# 2020_Example_USBController.net
KiCad netlist of a schematic drawn in EAGLE
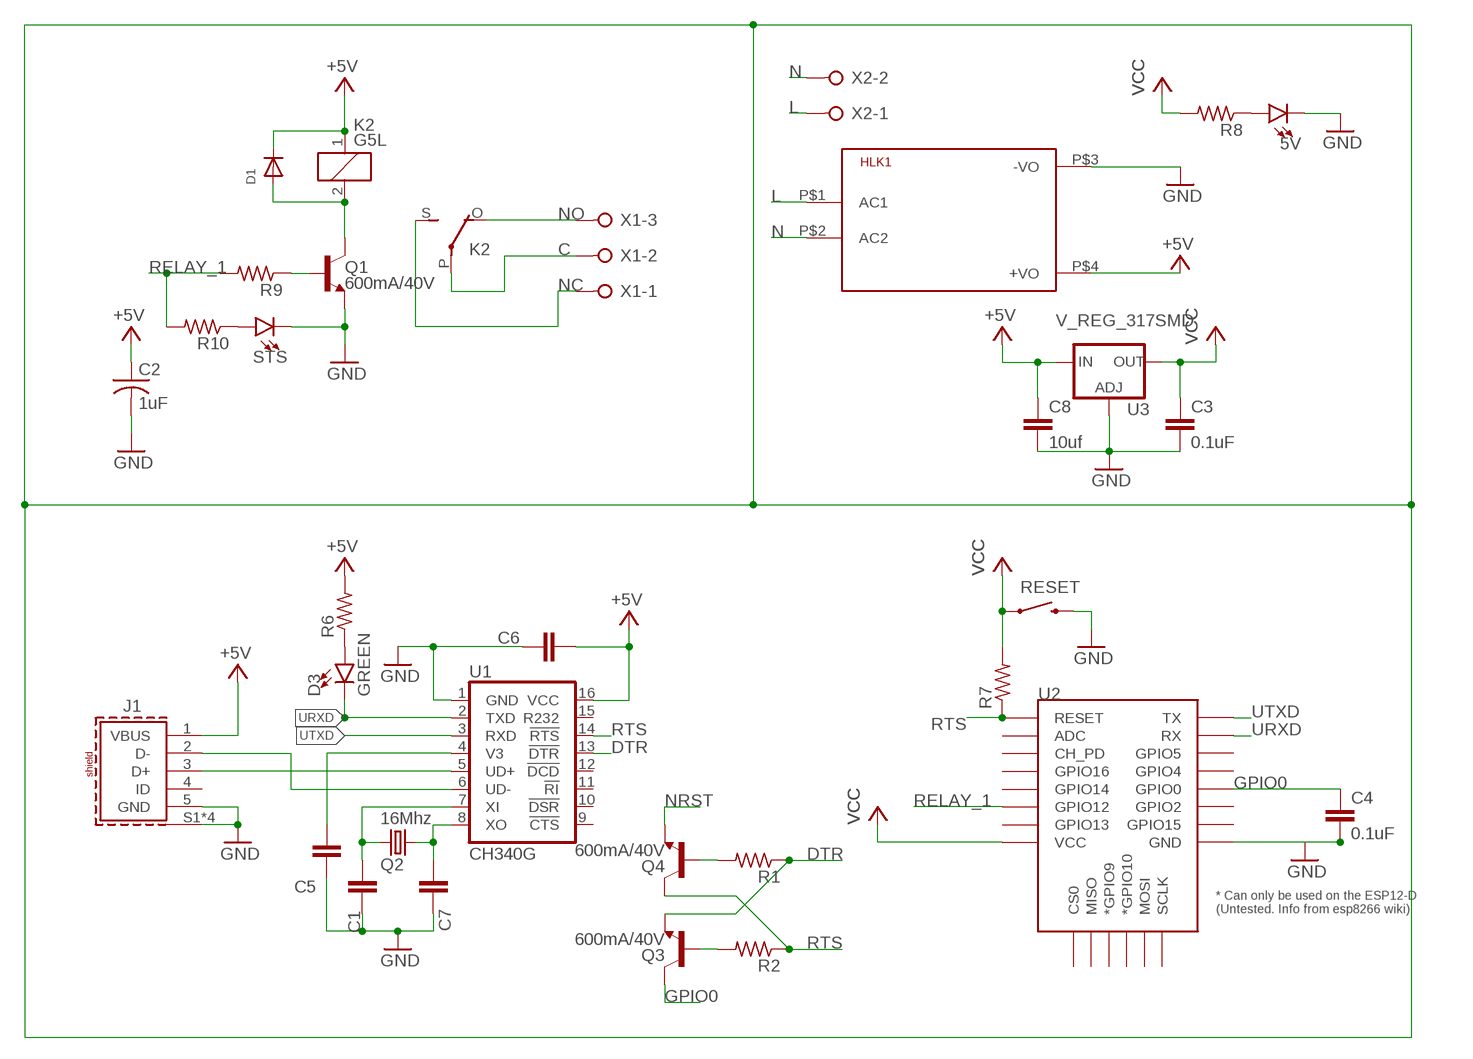
[diagram p0: schematic, sheet 1]

(export (version "E")
  (design (tool "Eeschema 10.0.6"))
  (components
    (comp (ref "5V")
      (value "LED-GREEN0603")
      (footprint "eagle-import:LED-0603")
      (libsource (lib "eagle-import") (part "LED-GREEN0603"))
    )
    (comp (ref "C1")
      (value "10pF")
      (footprint "eagle-import:C0805")
      (libsource (lib "eagle-import") (part "resistor_348_C-EUC0805"))
    )
    (comp (ref "C2")
      (value "1uF")
      (footprint "eagle-import:C0805K")
      (libsource (lib "eagle-import") (part "C-USC0805K"))
    )
    (comp (ref "C3")
      (value "0.1uF")
      (footprint "eagle-import:C0805")
      (libsource (lib "eagle-import") (part "C-EUC0805"))
    )
    (comp (ref "C4")
      (value "0.1uF")
      (footprint "eagle-import:C0805")
      (libsource (lib "eagle-import") (part "resistor_348_C-EUC0805"))
    )
    (comp (ref "C5")
      (value "10nF")
      (footprint "eagle-import:C0805")
      (libsource (lib "eagle-import") (part "resistor_348_C-EUC0805"))
    )
    (comp (ref "C6")
      (value "0.1uF")
      (footprint "eagle-import:C0805")
      (libsource (lib "eagle-import") (part "resistor_348_C-EUC0805"))
    )
    (comp (ref "C7")
      (value "10pF")
      (footprint "eagle-import:C0805")
      (libsource (lib "eagle-import") (part "resistor_348_C-EUC0805"))
    )
    (comp (ref "C8")
      (value "10uf")
      (footprint "eagle-import:C0805")
      (libsource (lib "eagle-import") (part "C-EUC0805"))
    )
    (comp (ref "D1")
      (value "DIODESOD-123")
      (footprint "eagle-import:SOD-123")
      (libsource (lib "eagle-import") (part "DIODESOD-123"))
    )
    (comp (ref "D3")
      (value "GREEN")
      (footprint "eagle-import:LED-0603")
      (libsource (lib "eagle-import") (part "LED-GREEN0603"))
    )
    (comp (ref "HLK1")
      (value "HLK-PM013W")
      (footprint "eagle-import:HLK-PM01")
      (libsource (lib "eagle-import") (part "HLK-PM013W"))
    )
    (comp (ref "J1")
      (value "629105150521")
      (footprint "eagle-import:629105150521")
      (libsource (lib "eagle-import") (part "629105150521"))
    )
    (comp (ref "K2")
      (value "G5L")
      (footprint "eagle-import:G5LE")
      (libsource (lib "eagle-import") (part "G5L"))
    )
    (comp (ref "Q1")
      (value "600mA/40V")
      (footprint "eagle-import:SOT23-3")
      (libsource (lib "eagle-import") (part "TRANS_NPN-MMBT2222AL"))
    )
    (comp (ref "Q2")
      (value "16Mhz")
      (footprint "eagle-import:5032_2P")
      (fields
        (field (name "MANUFACTURER") "Xinhunjing")
        (field (name "MPN") "5032/2P")
        (field (name "CREATED_BY") "PCBLayout.com")
      )
      (libsource (lib "eagle-import") (part "5032/2P"))
    )
    (comp (ref "Q3")
      (value "600mA/40V")
      (footprint "eagle-import:SOT23-3")
      (libsource (lib "eagle-import") (part "TRANS_NPN-MMBT2222AL"))
    )
    (comp (ref "Q4")
      (value "600mA/40V")
      (footprint "eagle-import:SOT23-3")
      (libsource (lib "eagle-import") (part "TRANS_NPN-MMBT2222AL"))
    )
    (comp (ref "R1")
      (value "R-US_R0805")
      (footprint "eagle-import:R0805")
      (libsource (lib "eagle-import") (part "R-US_R0805"))
    )
    (comp (ref "R2")
      (value "R-US_R0805")
      (footprint "eagle-import:R0805")
      (libsource (lib "eagle-import") (part "R-US_R0805"))
    )
    (comp (ref "R6")
      (value "R-US_R0805")
      (footprint "eagle-import:R0805")
      (libsource (lib "eagle-import") (part "R-US_R0805"))
    )
    (comp (ref "R7")
      (value "R-US_R0805")
      (footprint "eagle-import:R0805")
      (libsource (lib "eagle-import") (part "R-US_R0805"))
    )
    (comp (ref "R8")
      (value "R-US_R0805")
      (footprint "eagle-import:R0805")
      (libsource (lib "eagle-import") (part "R-US_R0805"))
    )
    (comp (ref "R9")
      (value "R-US_R0805")
      (footprint "eagle-import:R0805")
      (libsource (lib "eagle-import") (part "R-US_R0805"))
    )
    (comp (ref "R10")
      (value "R-US_R0805")
      (footprint "eagle-import:R0805")
      (libsource (lib "eagle-import") (part "R-US_R0805"))
    )
    (comp (ref "RESET")
      (value "RS032G05A3SM-SPST-MOMENTARY-SWSMD-1101NE")
      (footprint "eagle-import:TACTILE-SWITCH-1101NE")
      (libsource (lib "eagle-import") (part "RS032G05A3SM-SPST-MOMENTARY-SWSMD-1101NE"))
    )
    (comp (ref "STS")
      (value "LED-GREEN0603")
      (footprint "eagle-import:LED-0603")
      (libsource (lib "eagle-import") (part "LED-GREEN0603"))
    )
    (comp (ref "U1")
      (value "CH340G")
      (footprint "eagle-import:SO016")
      (libsource (lib "eagle-import") (part "CH340GSMD"))
    )
    (comp (ref "U2")
      (value "ESP12ESMD")
      (footprint "eagle-import:ESP12E-SMD")
      (libsource (lib "eagle-import") (part "ESP12ESMD"))
    )
    (comp (ref "U3")
      (value "V_REG_317SMD")
      (footprint "eagle-import:SOT223")
      (libsource (lib "eagle-import") (part "V_REG_317SMD"))
    )
    (comp (ref "X1")
      (value "W237-03P")
      (footprint "eagle-import:W237-133")
      (libsource (lib "eagle-import") (part "W237-03P"))
    )
    (comp (ref "X2")
      (value "W237-02P")
      (footprint "eagle-import:W237-132")
      (libsource (lib "eagle-import") (part "W237-02P"))
    )
  )
  (nets
    (net (code "1") (name "+5V") (class "Default")
      (node (ref "C2") (pin "1") (pinfunction "1_1") (pintype "passive"))
      (node (ref "C6") (pin "2") (pinfunction "2_2") (pintype "passive"))
      (node (ref "C8") (pin "1") (pinfunction "1_1") (pintype "passive"))
      (node (ref "D1") (pin "C") (pinfunction "C_C") (pintype "passive"))
      (node (ref "HLK1") (pin "P$4") (pinfunction "+VO_P$4") (pintype "bidirectional"))
      (node (ref "J1") (pin "1") (pinfunction "VBUS_1") (pintype "passive"))
      (node (ref "K2") (pin "1") (pinfunction "1_1") (pintype "passive"))
      (node (ref "R6") (pin "2") (pinfunction "2_2") (pintype "passive"))
      (node (ref "U1") (pin "16") (pinfunction "VCC_16") (pintype "bidirectional"))
      (node (ref "U3") (pin "3") (pinfunction "IN_3") (pintype "input"))
    )
    (net (code "2") (name "/C") (class "Default")
      (node (ref "K2") (pin "P") (pinfunction "P_P") (pintype "passive"))
      (node (ref "X1") (pin "2") (pinfunction "KL_2") (pintype "passive"))
    )
    (net (code "3") (name "/DTR") (class "Default")
      (node (ref "Q3") (pin "2") (pinfunction "E_2") (pintype "passive"))
      (node (ref "R1") (pin "1") (pinfunction "1_1") (pintype "passive"))
      (node (ref "U1") (pin "13") (pinfunction "~{DTR}_13") (pintype "bidirectional"))
    )
    (net (code "4") (name "/GPIO0") (class "Default")
      (node (ref "C4") (pin "1") (pinfunction "1_1") (pintype "passive"))
      (node (ref "Q3") (pin "3") (pinfunction "C_3") (pintype "passive"))
      (node (ref "U2") (pin "GPIO0") (pinfunction "GPIO0_GPIO0") (pintype "bidirectional"))
    )
    (net (code "5") (name "/L") (class "Default")
      (node (ref "HLK1") (pin "P$1") (pinfunction "AC1_P$1") (pintype "bidirectional"))
      (node (ref "X2") (pin "1") (pinfunction "KL_1") (pintype "passive"))
    )
    (net (code "6") (name "/N") (class "Default")
      (node (ref "HLK1") (pin "P$2") (pinfunction "AC2_P$2") (pintype "bidirectional"))
      (node (ref "X2") (pin "2") (pinfunction "KL_2") (pintype "passive"))
    )
    (net (code "7") (name "/NC") (class "Default")
      (node (ref "K2") (pin "S") (pinfunction "S_S") (pintype "passive"))
      (node (ref "X1") (pin "1") (pinfunction "KL_1") (pintype "passive"))
    )
    (net (code "8") (name "/NO") (class "Default")
      (node (ref "K2") (pin "O") (pinfunction "O_O") (pintype "passive"))
      (node (ref "X1") (pin "3") (pinfunction "KL_3") (pintype "passive"))
    )
    (net (code "9") (name "/NRST") (class "Default")
      (node (ref "Q4") (pin "2") (pinfunction "E_2") (pintype "passive"))
    )
    (net (code "10") (name "/RELAY_1") (class "Default")
      (node (ref "R10") (pin "2") (pinfunction "2_2") (pintype "passive"))
      (node (ref "R9") (pin "2") (pinfunction "2_2") (pintype "passive"))
      (node (ref "U2") (pin "GPIO12") (pinfunction "GPIO12_GPIO12") (pintype "bidirectional"))
    )
    (net (code "11") (name "/RTS") (class "Default")
      (node (ref "Q4") (pin "3") (pinfunction "C_3") (pintype "passive"))
      (node (ref "R2") (pin "1") (pinfunction "1_1") (pintype "passive"))
      (node (ref "R7") (pin "1") (pinfunction "1_1") (pintype "passive"))
      (node (ref "U1") (pin "14") (pinfunction "~{RTS}_14") (pintype "bidirectional"))
      (node (ref "U2") (pin "RESET") (pinfunction "RESET_RESET") (pintype "bidirectional"))
    )
    (net (code "12") (name "GND") (class "Default")
      (node (ref "5V") (pin "C") (pinfunction "C_C") (pintype "passive"))
      (node (ref "C1") (pin "1") (pinfunction "1_1") (pintype "passive"))
      (node (ref "C2") (pin "2") (pinfunction "2_2") (pintype "passive"))
      (node (ref "C3") (pin "2") (pinfunction "2_2") (pintype "passive"))
      (node (ref "C4") (pin "2") (pinfunction "2_2") (pintype "passive"))
      (node (ref "C5") (pin "1") (pinfunction "1_1") (pintype "passive"))
      (node (ref "C6") (pin "1") (pinfunction "1_1") (pintype "passive"))
      (node (ref "C7") (pin "1") (pinfunction "1_1") (pintype "passive"))
      (node (ref "C8") (pin "2") (pinfunction "2_2") (pintype "passive"))
      (node (ref "HLK1") (pin "P$3") (pinfunction "-VO_P$3") (pintype "bidirectional"))
      (node (ref "J1") (pin "5") (pinfunction "GND_5") (pintype "passive"))
      (node (ref "J1") (pin "S1") (pinfunction "SHIELD_S1") (pintype "passive"))
      (node (ref "J1") (pin "S2") (pinfunction "SHIELD_S2") (pintype "passive"))
      (node (ref "J1") (pin "S3") (pinfunction "SHIELD_S3") (pintype "passive"))
      (node (ref "J1") (pin "S4") (pinfunction "SHIELD_S4") (pintype "passive"))
      (node (ref "Q1") (pin "2") (pinfunction "E_2") (pintype "passive"))
      (node (ref "RESET") (pin "2") (pinfunction "2_2") (pintype "passive"))
      (node (ref "STS") (pin "C") (pinfunction "C_C") (pintype "passive"))
      (node (ref "U1") (pin "1") (pinfunction "GND_1") (pintype "bidirectional"))
      (node (ref "U2") (pin "GND") (pinfunction "GND_GND") (pintype "bidirectional"))
      (node (ref "U3") (pin "1") (pinfunction "ADJ_1") (pintype "input"))
    )
    (net (code "13") (name "Net-(5V-PadA)") (class "Default")
      (node (ref "5V") (pin "A") (pinfunction "A_A") (pintype "passive"))
      (node (ref "R8") (pin "1") (pinfunction "1_1") (pintype "passive"))
    )
    (net (code "14") (name "Net-(D3-PadA)") (class "Default")
      (node (ref "D3") (pin "A") (pinfunction "A_A") (pintype "passive"))
      (node (ref "R6") (pin "1") (pinfunction "1_1") (pintype "passive"))
    )
    (net (code "15") (name "Net-(J1-D+)") (class "Default")
      (node (ref "J1") (pin "3") (pinfunction "D+_3") (pintype "passive"))
      (node (ref "U1") (pin "5") (pinfunction "UD+_5") (pintype "bidirectional"))
    )
    (net (code "16") (name "Net-(J1-D-)") (class "Default")
      (node (ref "J1") (pin "2") (pinfunction "D-_2") (pintype "passive"))
      (node (ref "U1") (pin "6") (pinfunction "UD-_6") (pintype "bidirectional"))
    )
    (net (code "17") (name "Net-(Q1-B)") (class "Default")
      (node (ref "Q1") (pin "1") (pinfunction "B_1") (pintype "passive"))
      (node (ref "R9") (pin "1") (pinfunction "1_1") (pintype "passive"))
    )
    (net (code "18") (name "Net-(Q1-C)") (class "Default")
      (node (ref "D1") (pin "A") (pinfunction "A_A") (pintype "passive"))
      (node (ref "K2") (pin "2") (pinfunction "2_2") (pintype "passive"))
      (node (ref "Q1") (pin "3") (pinfunction "C_3") (pintype "passive"))
    )
    (net (code "19") (name "Net-(Q3-B)") (class "Default")
      (node (ref "Q3") (pin "1") (pinfunction "B_1") (pintype "passive"))
      (node (ref "R2") (pin "2") (pinfunction "2_2") (pintype "passive"))
    )
    (net (code "20") (name "Net-(Q4-B)") (class "Default")
      (node (ref "Q4") (pin "1") (pinfunction "B_1") (pintype "passive"))
      (node (ref "R1") (pin "2") (pinfunction "2_2") (pintype "passive"))
    )
    (net (code "21") (name "Net-(R10-Pad1)") (class "Default")
      (node (ref "R10") (pin "1") (pinfunction "1_1") (pintype "passive"))
      (node (ref "STS") (pin "A") (pinfunction "A_A") (pintype "passive"))
    )
    (net (code "22") (name "Net-(U1-V3)") (class "Default")
      (node (ref "C5") (pin "2") (pinfunction "2_2") (pintype "passive"))
      (node (ref "U1") (pin "4") (pinfunction "V3_4") (pintype "bidirectional"))
    )
    (net (code "23") (name "Net-(U1-XI)") (class "Default")
      (node (ref "C1") (pin "2") (pinfunction "2_2") (pintype "passive"))
      (node (ref "Q2") (pin "1") (pinfunction "1_1") (pintype "passive"))
      (node (ref "U1") (pin "7") (pinfunction "XI_7") (pintype "bidirectional"))
    )
    (net (code "24") (name "Net-(U1-XO)") (class "Default")
      (node (ref "C7") (pin "2") (pinfunction "2_2") (pintype "passive"))
      (node (ref "Q2") (pin "2") (pinfunction "2_2") (pintype "passive"))
      (node (ref "U1") (pin "8") (pinfunction "XO_8") (pintype "bidirectional"))
    )
    (net (code "25") (name "URXD") (class "Default")
      (node (ref "D3") (pin "C") (pinfunction "C_C") (pintype "passive"))
      (node (ref "U1") (pin "2") (pinfunction "TXD_2") (pintype "bidirectional"))
      (node (ref "U2") (pin "RXD0") (pinfunction "RX_RXD0") (pintype "bidirectional"))
    )
    (net (code "26") (name "UTXD") (class "Default")
      (node (ref "U1") (pin "3") (pinfunction "RXD_3") (pintype "bidirectional"))
      (node (ref "U2") (pin "TXD0") (pinfunction "TX_TXD0") (pintype "bidirectional"))
    )
    (net (code "27") (name "VCC") (class "Default")
      (node (ref "C3") (pin "1") (pinfunction "1_1") (pintype "passive"))
      (node (ref "R7") (pin "2") (pinfunction "2_2") (pintype "passive"))
      (node (ref "R8") (pin "2") (pinfunction "2_2") (pintype "passive"))
      (node (ref "RESET") (pin "1") (pinfunction "1_1") (pintype "passive"))
      (node (ref "U2") (pin "VCC") (pinfunction "VCC_VCC") (pintype "bidirectional"))
      (node (ref "U3") (pin "2") (pinfunction "OUT_2") (pintype "output"))
    )
    (net (code "28") (name "unconnected-(J1-ID-Pad4)") (class "Default")
      (node (ref "J1") (pin "4") (pinfunction "ID_4") (pintype "passive"))
    )
    (net (code "29") (name "unconnected-(U1-R232-Pad15)") (class "Default")
      (node (ref "U1") (pin "15") (pinfunction "R232_15") (pintype "bidirectional"))
    )
    (net (code "30") (name "unconnected-(U1-~{CTS}-Pad9)") (class "Default")
      (node (ref "U1") (pin "9") (pinfunction "~{CTS}_9") (pintype "bidirectional"))
    )
    (net (code "31") (name "unconnected-(U1-~{DCD}-Pad12)") (class "Default")
      (node (ref "U1") (pin "12") (pinfunction "~{DCD}_12") (pintype "bidirectional"))
    )
    (net (code "32") (name "unconnected-(U1-~{DSR}-Pad10)") (class "Default")
      (node (ref "U1") (pin "10") (pinfunction "~{DSR}_10") (pintype "bidirectional"))
    )
    (net (code "33") (name "unconnected-(U1-~{RI}-Pad11)") (class "Default")
      (node (ref "U1") (pin "11") (pinfunction "~{RI}_11") (pintype "bidirectional"))
    )
    (net (code "34") (name "unconnected-(U2-*GPIO9-PadGPIO9)") (class "Default")
      (node (ref "U2") (pin "GPIO9") (pinfunction "*GPIO9_GPIO9") (pintype "bidirectional"))
    )
    (net (code "35") (name "unconnected-(U2-*GPIO10-PadGPIO10)") (class "Default")
      (node (ref "U2") (pin "GPIO10") (pinfunction "*GPIO10_GPIO10") (pintype "bidirectional"))
    )
    (net (code "36") (name "unconnected-(U2-PadADC)") (class "Default")
      (node (ref "U2") (pin "ADC") (pinfunction "ADC_ADC") (pintype "bidirectional"))
    )
    (net (code "37") (name "unconnected-(U2-PadCH_PD)") (class "Default")
      (node (ref "U2") (pin "CH_PD") (pinfunction "CH_PD_CH_PD") (pintype "bidirectional"))
    )
    (net (code "38") (name "unconnected-(U2-PadCS0)") (class "Default")
      (node (ref "U2") (pin "CS0") (pinfunction "CS0_CS0") (pintype "bidirectional"))
    )
    (net (code "39") (name "unconnected-(U2-PadGPIO2)") (class "Default")
      (node (ref "U2") (pin "GPIO2") (pinfunction "GPIO2_GPIO2") (pintype "bidirectional"))
    )
    (net (code "40") (name "unconnected-(U2-PadGPIO4)") (class "Default")
      (node (ref "U2") (pin "GPIO4") (pinfunction "GPIO4_GPIO4") (pintype "bidirectional"))
    )
    (net (code "41") (name "unconnected-(U2-PadGPIO5)") (class "Default")
      (node (ref "U2") (pin "GPIO5") (pinfunction "GPIO5_GPIO5") (pintype "bidirectional"))
    )
    (net (code "42") (name "unconnected-(U2-PadGPIO13)") (class "Default")
      (node (ref "U2") (pin "GPIO13") (pinfunction "GPIO13_GPIO13") (pintype "bidirectional"))
    )
    (net (code "43") (name "unconnected-(U2-PadGPIO14)") (class "Default")
      (node (ref "U2") (pin "GPIO14") (pinfunction "GPIO14_GPIO14") (pintype "bidirectional"))
    )
    (net (code "44") (name "unconnected-(U2-PadGPIO15)") (class "Default")
      (node (ref "U2") (pin "GPIO15") (pinfunction "GPIO15_GPIO15") (pintype "bidirectional"))
    )
    (net (code "45") (name "unconnected-(U2-PadGPIO16)") (class "Default")
      (node (ref "U2") (pin "GPIO16") (pinfunction "GPIO16_GPIO16") (pintype "bidirectional"))
    )
    (net (code "46") (name "unconnected-(U2-PadMISO)") (class "Default")
      (node (ref "U2") (pin "MISO") (pinfunction "MISO_MISO") (pintype "bidirectional"))
    )
    (net (code "47") (name "unconnected-(U2-PadMOSI)") (class "Default")
      (node (ref "U2") (pin "MOSI") (pinfunction "MOSI_MOSI") (pintype "bidirectional"))
    )
    (net (code "48") (name "unconnected-(U2-PadSCLK)") (class "Default")
      (node (ref "U2") (pin "SCLK") (pinfunction "SCLK_SCLK") (pintype "bidirectional"))
    )
  )
)
